# figure-4-base.net
KiCad netlist of a schematic drawn in EAGLE
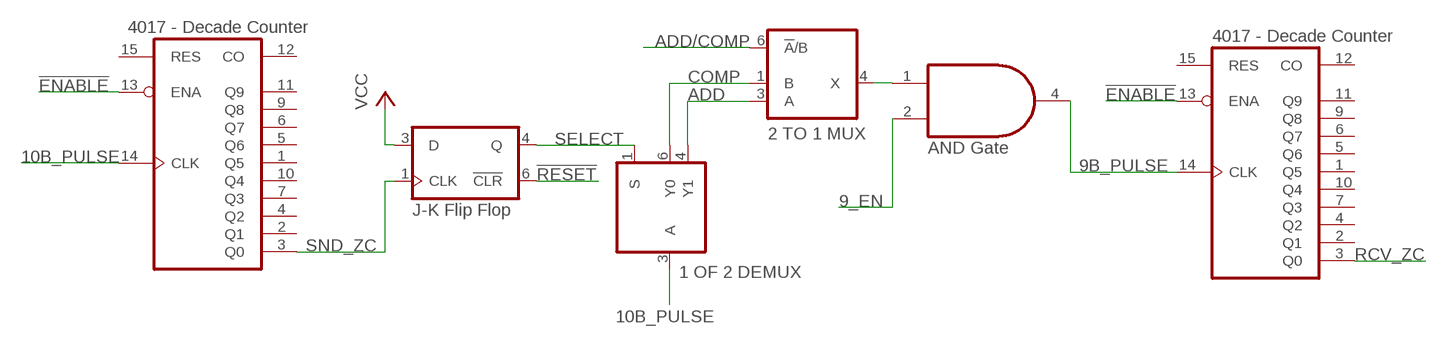
[diagram p0: schematic, sheet 1]
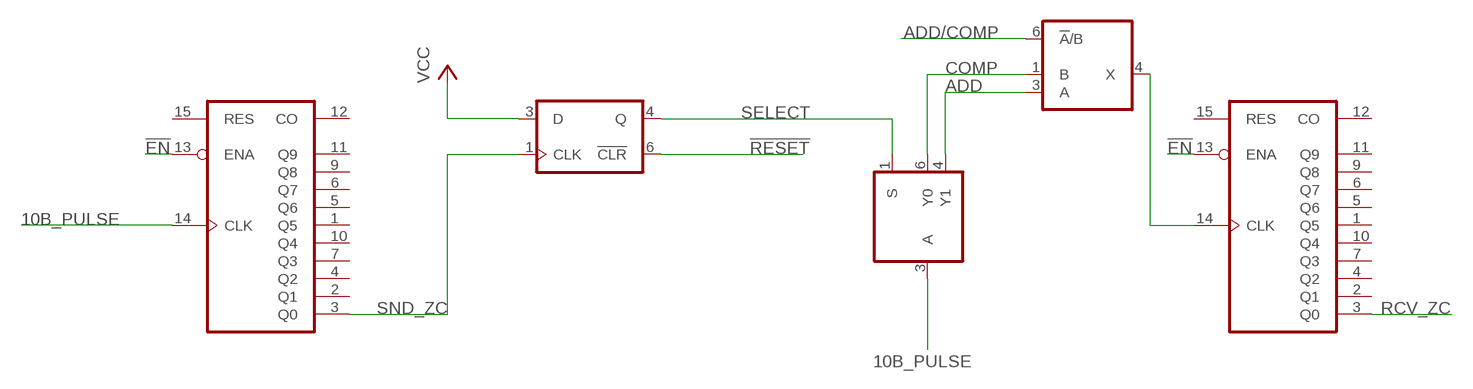
[diagram p1: schematic, sheet 2]

(export (version "E")
  (design (tool "Eeschema 10.0.6"))
  (components
    (comp (ref "IC1")
      (value "J-K Flip Flop")
      (footprint "eagle-import:DBV_R-PDSO-G6")
      (libsource (lib "eagle-import") (part "741G175"))
    )
    (comp (ref "IC3")
      (value "4017 - Decade Counter")
      (footprint "eagle-import:SO16")
      (libsource (lib "eagle-import") (part "4017D"))
    )
    (comp (ref "IC4")
      (value "1 OF 2 DEMUX")
      (footprint "eagle-import:DBV_R-PDSO-G6")
      (libsource (lib "eagle-import") (part "741G18"))
    )
    (comp (ref "IC6")
      (value "2 TO 1 MUX")
      (footprint "eagle-import:DBV_R-PDSO-G6")
      (libsource (lib "eagle-import") (part "741G3157DBVR"))
    )
    (comp (ref "IC9")
      (value "4017 - Decade Counter")
      (footprint "eagle-import:SO16")
      (libsource (lib "eagle-import") (part "4017D"))
    )
    (comp (ref "IC2")
      (value "1 OF 2 DEMUX")
      (footprint "eagle-import:DBV_R-PDSO-G6")
      (libsource (lib "eagle-import") (part "741G18"))
    )
    (comp (ref "IC5")
      (value "J-K Flip Flop")
      (footprint "eagle-import:DBV_R-PDSO-G6")
      (libsource (lib "eagle-import") (part "741G175"))
    )
    (comp (ref "IC7")
      (value "2 TO 1 MUX")
      (footprint "eagle-import:DBV_R-PDSO-G6")
      (libsource (lib "eagle-import") (part "741G3157DBVR"))
    )
    (comp (ref "IC8")
      (value "4017 - Decade Counter")
      (footprint "eagle-import:SO16")
      (libsource (lib "eagle-import") (part "4017D"))
    )
    (comp (ref "IC12")
      (value "4017 - Decade Counter")
      (footprint "eagle-import:SO16")
      (libsource (lib "eagle-import") (part "4017D"))
    )
    (comp (ref "IC13")
      (value "AND Gate")
      (footprint "eagle-import:SOT23-5")
      (libsource (lib "eagle-import") (part "741G08DBVLVC"))
    )
  )
  (nets
    (net (code "1") (name "9B_PULSE") (class "Default")
      (node (ref "IC12") (pin "14") (pinfunction "CLK_14") (pintype "input"))
      (node (ref "IC13") (pin "4") (pinfunction "O_4") (pintype "output"))
    )
    (net (code "2") (name "9_EN") (class "Default")
      (node (ref "IC13") (pin "2") (pinfunction "I1_2") (pintype "input"))
    )
    (net (code "3") (name "10B_PULSE") (class "Default")
      (node (ref "IC2") (pin "3") (pinfunction "A_3") (pintype "bidirectional"))
      (node (ref "IC3") (pin "14") (pinfunction "CLK_14") (pintype "input"))
      (node (ref "IC4") (pin "3") (pinfunction "A_3") (pintype "bidirectional"))
      (node (ref "IC8") (pin "14") (pinfunction "CLK_14") (pintype "input"))
    )
    (net (code "4") (name "ADD") (class "Default")
      (node (ref "IC2") (pin "4") (pinfunction "Y1_4") (pintype "bidirectional"))
      (node (ref "IC4") (pin "4") (pinfunction "Y1_4") (pintype "bidirectional"))
      (node (ref "IC6") (pin "3") (pinfunction "A_3") (pintype "bidirectional"))
      (node (ref "IC7") (pin "3") (pinfunction "A_3") (pintype "bidirectional"))
    )
    (net (code "5") (name "ADD{slash}COMP") (class "Default")
      (node (ref "IC6") (pin "6") (pinfunction "~{A}/B_6") (pintype "input"))
      (node (ref "IC7") (pin "6") (pinfunction "~{A}/B_6") (pintype "input"))
    )
    (net (code "6") (name "COMP") (class "Default")
      (node (ref "IC2") (pin "6") (pinfunction "Y0_6") (pintype "bidirectional"))
      (node (ref "IC4") (pin "6") (pinfunction "Y0_6") (pintype "bidirectional"))
      (node (ref "IC6") (pin "1") (pinfunction "B_1") (pintype "bidirectional"))
      (node (ref "IC7") (pin "1") (pinfunction "B_1") (pintype "bidirectional"))
    )
    (net (code "7") (name "Net-(IC6A-X)") (class "Default")
      (node (ref "IC6") (pin "4") (pinfunction "X_4") (pintype "bidirectional"))
      (node (ref "IC9") (pin "14") (pinfunction "CLK_14") (pintype "input"))
    )
    (net (code "8") (name "Net-(IC13A-I0)") (class "Default")
      (node (ref "IC13") (pin "1") (pinfunction "I0_1") (pintype "input"))
      (node (ref "IC7") (pin "4") (pinfunction "X_4") (pintype "bidirectional"))
    )
    (net (code "9") (name "RCV_ZC") (class "Default")
      (node (ref "IC12") (pin "3") (pinfunction "Q0_3") (pintype "output"))
      (node (ref "IC9") (pin "3") (pinfunction "Q0_3") (pintype "output"))
    )
    (net (code "10") (name "SELECT") (class "Default")
      (node (ref "IC1") (pin "4") (pinfunction "Q_4") (pintype "output"))
      (node (ref "IC2") (pin "1") (pinfunction "S_1") (pintype "input"))
      (node (ref "IC4") (pin "1") (pinfunction "S_1") (pintype "input"))
      (node (ref "IC5") (pin "4") (pinfunction "Q_4") (pintype "output"))
    )
    (net (code "11") (name "SND_ZC") (class "Default")
      (node (ref "IC1") (pin "1") (pinfunction "CLK_1") (pintype "input"))
      (node (ref "IC3") (pin "3") (pinfunction "Q0_3") (pintype "output"))
      (node (ref "IC5") (pin "1") (pinfunction "CLK_1") (pintype "input"))
      (node (ref "IC8") (pin "3") (pinfunction "Q0_3") (pintype "output"))
    )
    (net (code "12") (name "VCC") (class "Default")
      (node (ref "IC1") (pin "3") (pinfunction "D_3") (pintype "input"))
      (node (ref "IC5") (pin "3") (pinfunction "D_3") (pintype "input"))
    )
    (net (code "13") (name "unconnected-(IC3A-CO-Pad12)") (class "Default")
      (node (ref "IC3") (pin "12") (pinfunction "CO_12") (pintype "output"))
    )
    (net (code "14") (name "unconnected-(IC3A-Q1-Pad2)") (class "Default")
      (node (ref "IC3") (pin "2") (pinfunction "Q1_2") (pintype "output"))
    )
    (net (code "15") (name "unconnected-(IC3A-Q2-Pad4)") (class "Default")
      (node (ref "IC3") (pin "4") (pinfunction "Q2_4") (pintype "output"))
    )
    (net (code "16") (name "unconnected-(IC3A-Q3-Pad7)") (class "Default")
      (node (ref "IC3") (pin "7") (pinfunction "Q3_7") (pintype "output"))
    )
    (net (code "17") (name "unconnected-(IC3A-Q4-Pad10)") (class "Default")
      (node (ref "IC3") (pin "10") (pinfunction "Q4_10") (pintype "output"))
    )
    (net (code "18") (name "unconnected-(IC3A-Q5-Pad1)") (class "Default")
      (node (ref "IC3") (pin "1") (pinfunction "Q5_1") (pintype "output"))
    )
    (net (code "19") (name "unconnected-(IC3A-Q6-Pad5)") (class "Default")
      (node (ref "IC3") (pin "5") (pinfunction "Q6_5") (pintype "output"))
    )
    (net (code "20") (name "unconnected-(IC3A-Q7-Pad6)") (class "Default")
      (node (ref "IC3") (pin "6") (pinfunction "Q7_6") (pintype "output"))
    )
    (net (code "21") (name "unconnected-(IC3A-Q8-Pad9)") (class "Default")
      (node (ref "IC3") (pin "9") (pinfunction "Q8_9") (pintype "output"))
    )
    (net (code "22") (name "unconnected-(IC3A-Q9-Pad11)") (class "Default")
      (node (ref "IC3") (pin "11") (pinfunction "Q9_11") (pintype "output"))
    )
    (net (code "23") (name "unconnected-(IC3A-RES-Pad15)") (class "Default")
      (node (ref "IC3") (pin "15") (pinfunction "RES_15") (pintype "input"))
    )
    (net (code "24") (name "unconnected-(IC8A-CO-Pad12)") (class "Default")
      (node (ref "IC8") (pin "12") (pinfunction "CO_12") (pintype "output"))
    )
    (net (code "25") (name "unconnected-(IC8A-Q1-Pad2)") (class "Default")
      (node (ref "IC8") (pin "2") (pinfunction "Q1_2") (pintype "output"))
    )
    (net (code "26") (name "unconnected-(IC8A-Q2-Pad4)") (class "Default")
      (node (ref "IC8") (pin "4") (pinfunction "Q2_4") (pintype "output"))
    )
    (net (code "27") (name "unconnected-(IC8A-Q3-Pad7)") (class "Default")
      (node (ref "IC8") (pin "7") (pinfunction "Q3_7") (pintype "output"))
    )
    (net (code "28") (name "unconnected-(IC8A-Q4-Pad10)") (class "Default")
      (node (ref "IC8") (pin "10") (pinfunction "Q4_10") (pintype "output"))
    )
    (net (code "29") (name "unconnected-(IC8A-Q5-Pad1)") (class "Default")
      (node (ref "IC8") (pin "1") (pinfunction "Q5_1") (pintype "output"))
    )
    (net (code "30") (name "unconnected-(IC8A-Q6-Pad5)") (class "Default")
      (node (ref "IC8") (pin "5") (pinfunction "Q6_5") (pintype "output"))
    )
    (net (code "31") (name "unconnected-(IC8A-Q7-Pad6)") (class "Default")
      (node (ref "IC8") (pin "6") (pinfunction "Q7_6") (pintype "output"))
    )
    (net (code "32") (name "unconnected-(IC8A-Q8-Pad9)") (class "Default")
      (node (ref "IC8") (pin "9") (pinfunction "Q8_9") (pintype "output"))
    )
    (net (code "33") (name "unconnected-(IC8A-Q9-Pad11)") (class "Default")
      (node (ref "IC8") (pin "11") (pinfunction "Q9_11") (pintype "output"))
    )
    (net (code "34") (name "unconnected-(IC8A-RES-Pad15)") (class "Default")
      (node (ref "IC8") (pin "15") (pinfunction "RES_15") (pintype "input"))
    )
    (net (code "35") (name "unconnected-(IC9A-CO-Pad12)") (class "Default")
      (node (ref "IC9") (pin "12") (pinfunction "CO_12") (pintype "output"))
    )
    (net (code "36") (name "unconnected-(IC9A-Q1-Pad2)") (class "Default")
      (node (ref "IC9") (pin "2") (pinfunction "Q1_2") (pintype "output"))
    )
    (net (code "37") (name "unconnected-(IC9A-Q2-Pad4)") (class "Default")
      (node (ref "IC9") (pin "4") (pinfunction "Q2_4") (pintype "output"))
    )
    (net (code "38") (name "unconnected-(IC9A-Q3-Pad7)") (class "Default")
      (node (ref "IC9") (pin "7") (pinfunction "Q3_7") (pintype "output"))
    )
    (net (code "39") (name "unconnected-(IC9A-Q4-Pad10)") (class "Default")
      (node (ref "IC9") (pin "10") (pinfunction "Q4_10") (pintype "output"))
    )
    (net (code "40") (name "unconnected-(IC9A-Q5-Pad1)") (class "Default")
      (node (ref "IC9") (pin "1") (pinfunction "Q5_1") (pintype "output"))
    )
    (net (code "41") (name "unconnected-(IC9A-Q6-Pad5)") (class "Default")
      (node (ref "IC9") (pin "5") (pinfunction "Q6_5") (pintype "output"))
    )
    (net (code "42") (name "unconnected-(IC9A-Q7-Pad6)") (class "Default")
      (node (ref "IC9") (pin "6") (pinfunction "Q7_6") (pintype "output"))
    )
    (net (code "43") (name "unconnected-(IC9A-Q8-Pad9)") (class "Default")
      (node (ref "IC9") (pin "9") (pinfunction "Q8_9") (pintype "output"))
    )
    (net (code "44") (name "unconnected-(IC9A-Q9-Pad11)") (class "Default")
      (node (ref "IC9") (pin "11") (pinfunction "Q9_11") (pintype "output"))
    )
    (net (code "45") (name "unconnected-(IC9A-RES-Pad15)") (class "Default")
      (node (ref "IC9") (pin "15") (pinfunction "RES_15") (pintype "input"))
    )
    (net (code "46") (name "unconnected-(IC12A-CO-Pad12)") (class "Default")
      (node (ref "IC12") (pin "12") (pinfunction "CO_12") (pintype "output"))
    )
    (net (code "47") (name "unconnected-(IC12A-Q1-Pad2)") (class "Default")
      (node (ref "IC12") (pin "2") (pinfunction "Q1_2") (pintype "output"))
    )
    (net (code "48") (name "unconnected-(IC12A-Q2-Pad4)") (class "Default")
      (node (ref "IC12") (pin "4") (pinfunction "Q2_4") (pintype "output"))
    )
    (net (code "49") (name "unconnected-(IC12A-Q3-Pad7)") (class "Default")
      (node (ref "IC12") (pin "7") (pinfunction "Q3_7") (pintype "output"))
    )
    (net (code "50") (name "unconnected-(IC12A-Q4-Pad10)") (class "Default")
      (node (ref "IC12") (pin "10") (pinfunction "Q4_10") (pintype "output"))
    )
    (net (code "51") (name "unconnected-(IC12A-Q5-Pad1)") (class "Default")
      (node (ref "IC12") (pin "1") (pinfunction "Q5_1") (pintype "output"))
    )
    (net (code "52") (name "unconnected-(IC12A-Q6-Pad5)") (class "Default")
      (node (ref "IC12") (pin "5") (pinfunction "Q6_5") (pintype "output"))
    )
    (net (code "53") (name "unconnected-(IC12A-Q7-Pad6)") (class "Default")
      (node (ref "IC12") (pin "6") (pinfunction "Q7_6") (pintype "output"))
    )
    (net (code "54") (name "unconnected-(IC12A-Q8-Pad9)") (class "Default")
      (node (ref "IC12") (pin "9") (pinfunction "Q8_9") (pintype "output"))
    )
    (net (code "55") (name "unconnected-(IC12A-Q9-Pad11)") (class "Default")
      (node (ref "IC12") (pin "11") (pinfunction "Q9_11") (pintype "output"))
    )
    (net (code "56") (name "unconnected-(IC12A-RES-Pad15)") (class "Default")
      (node (ref "IC12") (pin "15") (pinfunction "RES_15") (pintype "input"))
    )
    (net (code "57") (name "~{ENABLE}") (class "Default")
      (node (ref "IC12") (pin "13") (pinfunction "ENA_13") (pintype "input"))
      (node (ref "IC8") (pin "13") (pinfunction "ENA_13") (pintype "input"))
    )
    (net (code "58") (name "~{EN}") (class "Default")
      (node (ref "IC3") (pin "13") (pinfunction "ENA_13") (pintype "input"))
      (node (ref "IC9") (pin "13") (pinfunction "ENA_13") (pintype "input"))
    )
    (net (code "59") (name "~{RESET}") (class "Default")
      (node (ref "IC1") (pin "6") (pinfunction "~{CLR}_6") (pintype "input"))
      (node (ref "IC5") (pin "6") (pinfunction "~{CLR}_6") (pintype "input"))
    )
  )
)
